# 07_RFID_LCD.net
KiCad netlist of a schematic drawn in Altium Designer
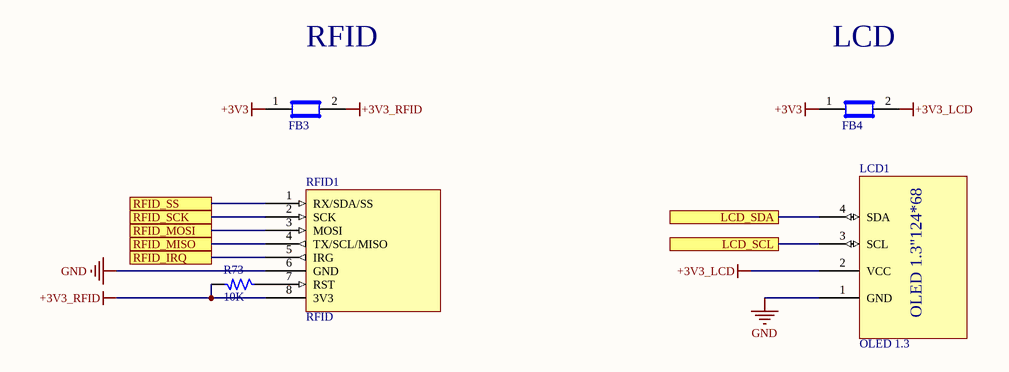
[diagram p0: [07]RFID_LCD.SchDoc]

(export (version "E")
  (design (tool "Eeschema 10.0.6"))
  (components
    (comp (ref "FB3")
      (value "BLM21PG600SN1D")
      (footprint "R0805")
      (description "Ferrite Bead")
      (libsource (lib "GPS_Traking_V1_1") (part "Ferrite Bead"))
    )
    (comp (ref "FB4")
      (value "BLM21PG600SN1D")
      (footprint "R0805")
      (description "Ferrite Bead")
      (libsource (lib "GPS_Traking_V1_1") (part "Ferrite Bead"))
    )
    (comp (ref "LCD1")
      (value "OLED 1.3")
      (footprint "CON_4P")
      (libsource (lib "My Library") (part "OLED 1.3"))
    )
    (comp (ref "R73")
      (value "10K")
      (footprint "RES-SMD-0805")
      (description "Resistor SMD")
      (libsource (lib "GPS_Traking_V1_1") (part "RM"))
    )
    (comp (ref "RFID1")
      (value "RFID")
      (footprint "RFID RC522")
      (libsource (lib "My Library") (part "RFID RC522"))
    )
  )
  (nets
    (net (code "1") (name "+3V3") (class "Default")
      (node (ref "FB3") (pin "1") (pinfunction "1_1") (pintype "passive"))
      (node (ref "FB4") (pin "1") (pinfunction "1_1") (pintype "passive"))
    )
    (net (code "2") (name "+3V3_LCD") (class "Default")
      (node (ref "FB4") (pin "2") (pinfunction "2_2") (pintype "passive"))
      (node (ref "LCD1") (pin "2") (pinfunction "VCC_2") (pintype "power_in"))
    )
    (net (code "3") (name "+3V3_RFID") (class "Default")
      (node (ref "FB3") (pin "2") (pinfunction "2_2") (pintype "passive"))
      (node (ref "R73") (pin "2") (pinfunction "2_2") (pintype "passive"))
      (node (ref "RFID1") (pin "8") (pinfunction "3V3_8") (pintype "power_in"))
    )
    (net (code "4") (name "/LCD_SCL") (class "Default")
      (node (ref "LCD1") (pin "3") (pinfunction "SCL_3") (pintype "bidirectional"))
    )
    (net (code "5") (name "/LCD_SDA") (class "Default")
      (node (ref "LCD1") (pin "4") (pinfunction "SDA_4") (pintype "bidirectional"))
    )
    (net (code "6") (name "/RFID_IRQ") (class "Default")
      (node (ref "RFID1") (pin "5") (pinfunction "IRG_5") (pintype "output"))
    )
    (net (code "7") (name "/RFID_MISO") (class "Default")
      (node (ref "RFID1") (pin "4") (pinfunction "TX/SCL/MISO_4") (pintype "output"))
    )
    (net (code "8") (name "/RFID_MOSI") (class "Default")
      (node (ref "RFID1") (pin "3") (pinfunction "MOSI_3") (pintype "input"))
    )
    (net (code "9") (name "/RFID_SCK") (class "Default")
      (node (ref "RFID1") (pin "2") (pinfunction "SCK_2") (pintype "input"))
    )
    (net (code "10") (name "/RFID_SS") (class "Default")
      (node (ref "RFID1") (pin "1") (pinfunction "RX/SDA/SS_1") (pintype "input"))
    )
    (net (code "11") (name "GND") (class "Default")
      (node (ref "LCD1") (pin "1") (pinfunction "GND_1") (pintype "power_in"))
      (node (ref "RFID1") (pin "6") (pinfunction "GND_6") (pintype "power_in"))
    )
    (net (code "12") (name "Net-(RFID1-RST)") (class "Default")
      (node (ref "R73") (pin "1") (pinfunction "1_1") (pintype "passive"))
      (node (ref "RFID1") (pin "7") (pinfunction "RST_7") (pintype "input"))
    )
  )
)
